# PMOD_IO.net
KiCad netlist of a schematic drawn in Altium Designer
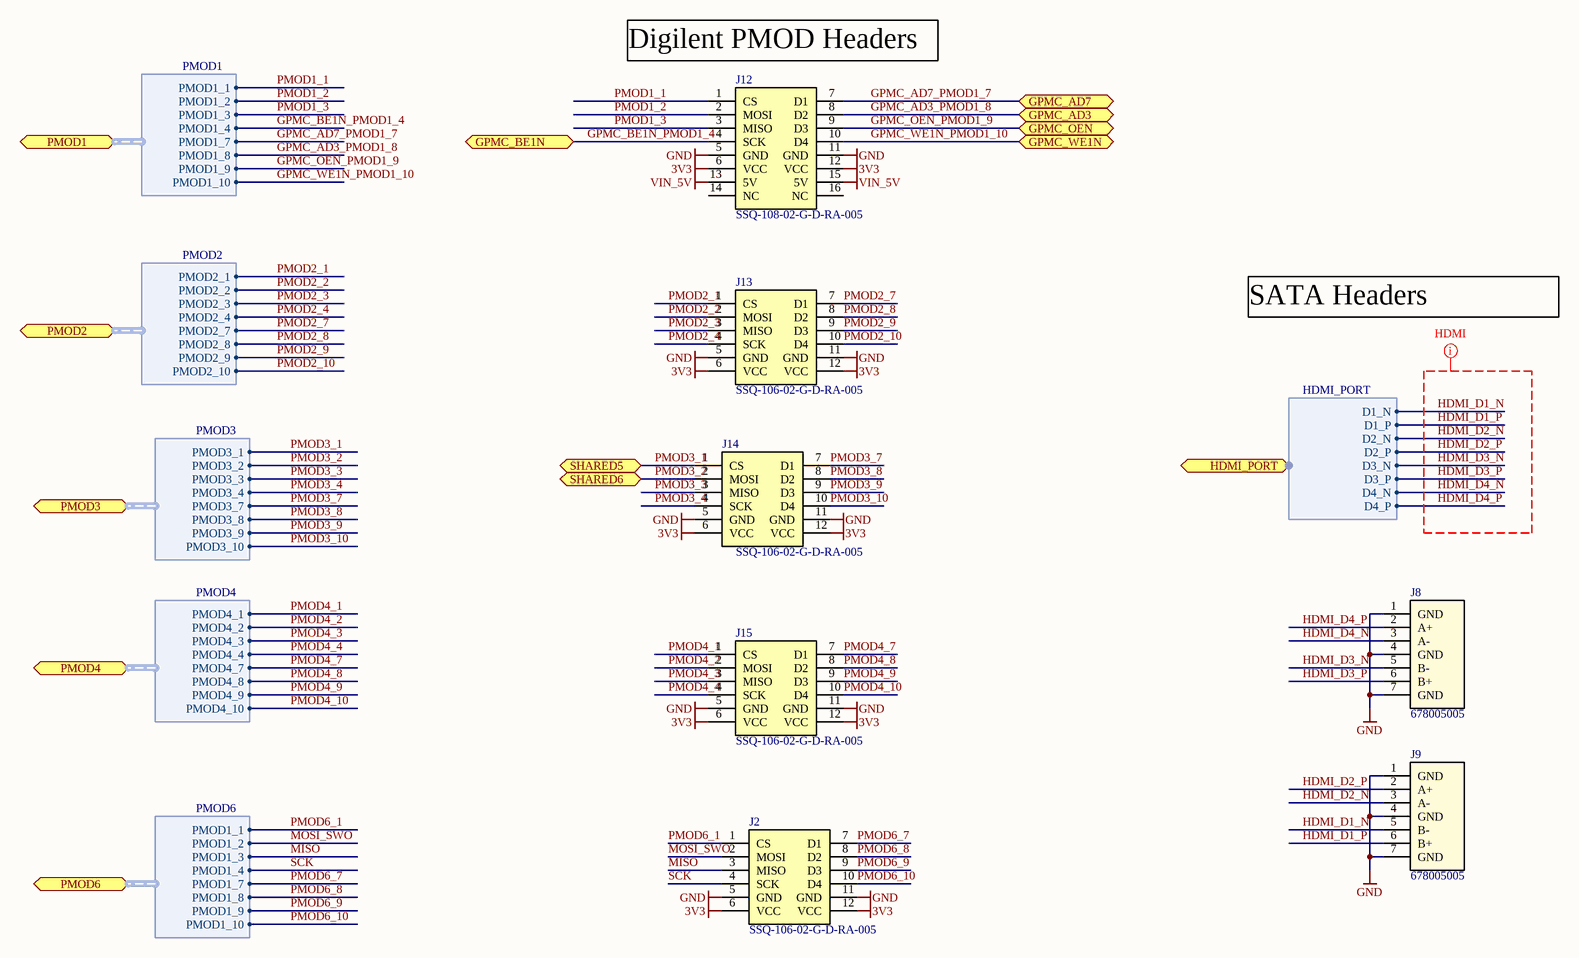
[diagram p0: PMOD_IO.SchDoc]

(export (version "E")
  (design (tool "Eeschema 10.0.6"))
  (components
    (comp (ref "J2")
      (value "SSQ-106-02-G-D-RA-005")
      (footprint "PMOD HEADER - SSQ-106-02-G-D-RA")
      (description "SAMTEC - SSQ-106-02-G-D-RA-005 - 2MM SOCKET STRIPS")
      (fields (field (name "MANUFACTURER") "SAMTEC"))
      (libsource (lib "mConnector") (part "P-MOD - SSQ-106-02-G-D-RA-005"))
    )
    (comp (ref "J8")
      (value "678005005")
      (footprint "SATA - 67800-5005")
      (description "I/O Connectors 7Ckt Vert Signal Hdr SMT w/ locking latch")
      (fields (field (name "MANUFACTURER") "Molex") (field (name "MANUFACTURER PART NUMBER") "67800-5005"))
      (libsource (lib "mConnector") (part "SATA - 67800-5005"))
    )
    (comp (ref "J9")
      (value "678005005")
      (footprint "SATA - 67800-5005")
      (description "I/O Connectors 7Ckt Vert Signal Hdr SMT w/ locking latch")
      (fields (field (name "MANUFACTURER") "Molex") (field (name "MANUFACTURER PART NUMBER") "67800-5005"))
      (libsource (lib "mConnector") (part "SATA - 67800-5005"))
    )
    (comp (ref "J12")
      (value "SSQ-108-02-G-D-RA-005")
      (footprint "PMOD HEADER8 - SSQ-108-02-G-D-RA")
      (description "SAMTEC - SSQ-108-02-G-D-RA-005 - 2MM SOCKET STRIPS")
      (fields (field (name "MANUFACTURER") "SAMTEC"))
      (libsource (lib "mConnector") (part "P-MOD - SSQ-108-02-G-D-RA-005"))
    )
    (comp (ref "J13")
      (value "SSQ-106-02-G-D-RA-005")
      (footprint "PMOD HEADER - SSQ-106-02-G-D-RA")
      (description "SAMTEC - SSQ-106-02-G-D-RA-005 - 2MM SOCKET STRIPS")
      (fields (field (name "MANUFACTURER") "SAMTEC"))
      (libsource (lib "mConnector") (part "P-MOD - SSQ-106-02-G-D-RA-005"))
    )
    (comp (ref "J14")
      (value "SSQ-106-02-G-D-RA-005")
      (footprint "PMOD HEADER - SSQ-106-02-G-D-RA")
      (description "SAMTEC - SSQ-106-02-G-D-RA-005 - 2MM SOCKET STRIPS")
      (fields (field (name "MANUFACTURER") "SAMTEC"))
      (libsource (lib "mConnector") (part "P-MOD - SSQ-106-02-G-D-RA-005"))
    )
    (comp (ref "J15")
      (value "SSQ-106-02-G-D-RA-005")
      (footprint "PMOD HEADER - SSQ-106-02-G-D-RA")
      (description "SAMTEC - SSQ-106-02-G-D-RA-005 - 2MM SOCKET STRIPS")
      (fields (field (name "MANUFACTURER") "SAMTEC"))
      (libsource (lib "mConnector") (part "P-MOD - SSQ-106-02-G-D-RA-005"))
    )
  )
  (nets
    (net (code "7") (name "/GPMC_AD3_PMOD1_8") (class "Default")
      (node (ref "J12") (pin "8") (pinfunction "D2_8") (pintype "power_in"))
    )
    (net (code "8") (name "/GPMC_AD7_PMOD1_7") (class "Default")
      (node (ref "J12") (pin "7") (pinfunction "D1_7") (pintype "power_in"))
    )
    (net (code "9") (name "/GPMC_BE1N_PMOD1_4") (class "Default")
      (node (ref "J12") (pin "4") (pinfunction "SCK_4") (pintype "power_in"))
    )
    (net (code "10") (name "/GPMC_OEN_PMOD1_9") (class "Default")
      (node (ref "J12") (pin "9") (pinfunction "D3_9") (pintype "power_in"))
    )
    (net (code "11") (name "/GPMC_WE1N_PMOD1_10") (class "Default")
      (node (ref "J12") (pin "10") (pinfunction "D4_10") (pintype "power_in"))
    )
    (net (code "12") (name "/HDMI_D1_N") (class "Default")
      (node (ref "J9") (pin "5") (pinfunction "B-_5") (pintype "passive"))
    )
    (net (code "13") (name "/HDMI_D1_P") (class "Default")
      (node (ref "J9") (pin "6") (pinfunction "B+_6") (pintype "passive"))
    )
    (net (code "14") (name "/HDMI_D2_N") (class "Default")
      (node (ref "J9") (pin "3") (pinfunction "A-_3") (pintype "passive"))
    )
    (net (code "15") (name "/HDMI_D2_P") (class "Default")
      (node (ref "J9") (pin "2") (pinfunction "A+_2") (pintype "passive"))
    )
    (net (code "16") (name "/HDMI_D3_N") (class "Default")
      (node (ref "J8") (pin "5") (pinfunction "B-_5") (pintype "passive"))
    )
    (net (code "17") (name "/HDMI_D3_P") (class "Default")
      (node (ref "J8") (pin "6") (pinfunction "B+_6") (pintype "passive"))
    )
    (net (code "18") (name "/HDMI_D4_N") (class "Default")
      (node (ref "J8") (pin "3") (pinfunction "A-_3") (pintype "passive"))
    )
    (net (code "19") (name "/HDMI_D4_P") (class "Default")
      (node (ref "J8") (pin "2") (pinfunction "A+_2") (pintype "passive"))
    )
    (net (code "20") (name "/MISO") (class "Default")
      (node (ref "J2") (pin "3") (pinfunction "MISO_3") (pintype "power_in"))
    )
    (net (code "21") (name "/MOSI_SWO") (class "Default")
      (node (ref "J2") (pin "2") (pinfunction "MOSI_2") (pintype "power_in"))
    )
    (net (code "22") (name "/PMOD1_1") (class "Default")
      (node (ref "J12") (pin "1") (pinfunction "CS_1") (pintype "power_in"))
    )
    (net (code "23") (name "/PMOD1_2") (class "Default")
      (node (ref "J12") (pin "2") (pinfunction "MOSI_2") (pintype "power_in"))
    )
    (net (code "24") (name "/PMOD1_3") (class "Default")
      (node (ref "J12") (pin "3") (pinfunction "MISO_3") (pintype "power_in"))
    )
    (net (code "25") (name "/PMOD2_1") (class "Default")
      (node (ref "J13") (pin "1") (pinfunction "CS_1") (pintype "power_in"))
    )
    (net (code "26") (name "/PMOD2_2") (class "Default")
      (node (ref "J13") (pin "2") (pinfunction "MOSI_2") (pintype "power_in"))
    )
    (net (code "27") (name "/PMOD2_3") (class "Default")
      (node (ref "J13") (pin "3") (pinfunction "MISO_3") (pintype "power_in"))
    )
    (net (code "28") (name "/PMOD2_4") (class "Default")
      (node (ref "J13") (pin "4") (pinfunction "SCK_4") (pintype "power_in"))
    )
    (net (code "29") (name "/PMOD2_7") (class "Default")
      (node (ref "J13") (pin "7") (pinfunction "D1_7") (pintype "power_in"))
    )
    (net (code "30") (name "/PMOD2_8") (class "Default")
      (node (ref "J13") (pin "8") (pinfunction "D2_8") (pintype "power_in"))
    )
    (net (code "31") (name "/PMOD2_9") (class "Default")
      (node (ref "J13") (pin "9") (pinfunction "D3_9") (pintype "power_in"))
    )
    (net (code "32") (name "/PMOD2_10") (class "Default")
      (node (ref "J13") (pin "10") (pinfunction "D4_10") (pintype "power_in"))
    )
    (net (code "33") (name "/PMOD3_1") (class "Default")
      (node (ref "J14") (pin "1") (pinfunction "CS_1") (pintype "power_in"))
    )
    (net (code "34") (name "/PMOD3_2") (class "Default")
      (node (ref "J14") (pin "2") (pinfunction "MOSI_2") (pintype "power_in"))
    )
    (net (code "35") (name "/PMOD3_3") (class "Default")
      (node (ref "J14") (pin "3") (pinfunction "MISO_3") (pintype "power_in"))
    )
    (net (code "36") (name "/PMOD3_4") (class "Default")
      (node (ref "J14") (pin "4") (pinfunction "SCK_4") (pintype "power_in"))
    )
    (net (code "37") (name "/PMOD3_7") (class "Default")
      (node (ref "J14") (pin "7") (pinfunction "D1_7") (pintype "power_in"))
    )
    (net (code "38") (name "/PMOD3_8") (class "Default")
      (node (ref "J14") (pin "8") (pinfunction "D2_8") (pintype "power_in"))
    )
    (net (code "39") (name "/PMOD3_9") (class "Default")
      (node (ref "J14") (pin "9") (pinfunction "D3_9") (pintype "power_in"))
    )
    (net (code "40") (name "/PMOD3_10") (class "Default")
      (node (ref "J14") (pin "10") (pinfunction "D4_10") (pintype "power_in"))
    )
    (net (code "41") (name "/PMOD4_1") (class "Default")
      (node (ref "J15") (pin "1") (pinfunction "CS_1") (pintype "power_in"))
    )
    (net (code "42") (name "/PMOD4_2") (class "Default")
      (node (ref "J15") (pin "2") (pinfunction "MOSI_2") (pintype "power_in"))
    )
    (net (code "43") (name "/PMOD4_3") (class "Default")
      (node (ref "J15") (pin "3") (pinfunction "MISO_3") (pintype "power_in"))
    )
    (net (code "44") (name "/PMOD4_4") (class "Default")
      (node (ref "J15") (pin "4") (pinfunction "SCK_4") (pintype "power_in"))
    )
    (net (code "45") (name "/PMOD4_7") (class "Default")
      (node (ref "J15") (pin "7") (pinfunction "D1_7") (pintype "power_in"))
    )
    (net (code "46") (name "/PMOD4_8") (class "Default")
      (node (ref "J15") (pin "8") (pinfunction "D2_8") (pintype "power_in"))
    )
    (net (code "47") (name "/PMOD4_9") (class "Default")
      (node (ref "J15") (pin "9") (pinfunction "D3_9") (pintype "power_in"))
    )
    (net (code "48") (name "/PMOD4_10") (class "Default")
      (node (ref "J15") (pin "10") (pinfunction "D4_10") (pintype "power_in"))
    )
    (net (code "49") (name "/PMOD6_1") (class "Default")
      (node (ref "J2") (pin "1") (pinfunction "CS_1") (pintype "power_in"))
    )
    (net (code "50") (name "/PMOD6_7") (class "Default")
      (node (ref "J2") (pin "7") (pinfunction "D1_7") (pintype "power_in"))
    )
    (net (code "51") (name "/PMOD6_8") (class "Default")
      (node (ref "J2") (pin "8") (pinfunction "D2_8") (pintype "power_in"))
    )
    (net (code "52") (name "/PMOD6_9") (class "Default")
      (node (ref "J2") (pin "9") (pinfunction "D3_9") (pintype "power_in"))
    )
    (net (code "53") (name "/PMOD6_10") (class "Default")
      (node (ref "J2") (pin "10") (pinfunction "D4_10") (pintype "power_in"))
    )
    (net (code "54") (name "/SCK") (class "Default")
      (node (ref "J2") (pin "4") (pinfunction "SCK_4") (pintype "power_in"))
    )
    (net (code "61") (name "3V3") (class "Default")
      (node (ref "J12") (pin "12") (pinfunction "VCC_12") (pintype "power_in"))
      (node (ref "J12") (pin "6") (pinfunction "VCC_6") (pintype "power_in"))
      (node (ref "J13") (pin "12") (pinfunction "VCC_12") (pintype "power_in"))
      (node (ref "J13") (pin "6") (pinfunction "VCC_6") (pintype "power_in"))
      (node (ref "J14") (pin "12") (pinfunction "VCC_12") (pintype "power_in"))
      (node (ref "J14") (pin "6") (pinfunction "VCC_6") (pintype "power_in"))
      (node (ref "J15") (pin "12") (pinfunction "VCC_12") (pintype "power_in"))
      (node (ref "J15") (pin "6") (pinfunction "VCC_6") (pintype "power_in"))
      (node (ref "J2") (pin "12") (pinfunction "VCC_12") (pintype "power_in"))
      (node (ref "J2") (pin "6") (pinfunction "VCC_6") (pintype "power_in"))
    )
    (net (code "62") (name "GND") (class "Default")
      (node (ref "J12") (pin "11") (pinfunction "GND_11") (pintype "power_in"))
      (node (ref "J12") (pin "5") (pinfunction "GND_5") (pintype "power_in"))
      (node (ref "J13") (pin "11") (pinfunction "GND_11") (pintype "power_in"))
      (node (ref "J13") (pin "5") (pinfunction "GND_5") (pintype "power_in"))
      (node (ref "J14") (pin "11") (pinfunction "GND_11") (pintype "power_in"))
      (node (ref "J14") (pin "5") (pinfunction "GND_5") (pintype "power_in"))
      (node (ref "J15") (pin "11") (pinfunction "GND_11") (pintype "power_in"))
      (node (ref "J15") (pin "5") (pinfunction "GND_5") (pintype "power_in"))
      (node (ref "J2") (pin "11") (pinfunction "GND_11") (pintype "power_in"))
      (node (ref "J2") (pin "5") (pinfunction "GND_5") (pintype "power_in"))
      (node (ref "J8") (pin "1") (pinfunction "GND_1") (pintype "passive"))
      (node (ref "J8") (pin "4") (pinfunction "GND_4") (pintype "passive"))
      (node (ref "J8") (pin "7") (pinfunction "GND_7") (pintype "passive"))
      (node (ref "J9") (pin "1") (pinfunction "GND_1") (pintype "passive"))
      (node (ref "J9") (pin "4") (pinfunction "GND_4") (pintype "passive"))
      (node (ref "J9") (pin "7") (pinfunction "GND_7") (pintype "passive"))
    )
    (net (code "63") (name "VIN_5V") (class "Default")
      (node (ref "J12") (pin "13") (pinfunction "5V_13") (pintype "power_in"))
      (node (ref "J12") (pin "15") (pinfunction "5V_15") (pintype "power_in"))
    )
    (net (code "64") (name "unconnected-(J12-NC-Pad14)") (class "Default")
      (node (ref "J12") (pin "14") (pinfunction "NC_14") (pintype "power_in"))
    )
    (net (code "65") (name "unconnected-(J12-NC-Pad16)") (class "Default")
      (node (ref "J12") (pin "16") (pinfunction "NC_16") (pintype "power_in"))
    )
  )
)
